# Power.net
KiCad netlist of a schematic drawn in Altium Designer
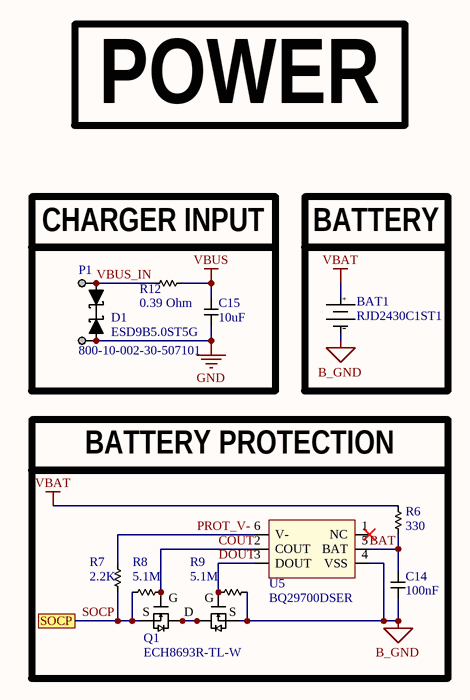
[diagram p0: Power.SchDoc]

(export (version "E")
  (design (tool "Eeschema 10.0.6"))
  (components
    (comp (ref "BAT1")
      (value "RJD2430C1ST1")
      (footprint "RJD2430C1ST1")
      (description "Coin, 24.5mm 3.7V Lithium-Ion Battery Rechargeable (Secondary) 110mAh")
      (libsource (lib "smLib") (part "RJD2430C1ST1"))
    )
    (comp (ref "C14")
      (value "100nF")
      (footprint "CAP_0603_HIGH")
      (description "0603 Capacitor")
      (libsource (lib "smLib") (part "Capacitor_0603"))
    )
    (comp (ref "C15")
      (value "10uF")
      (footprint "CAP_0603_HIGH")
      (description "0603 Capacitor")
      (libsource (lib "smLib") (part "Capacitor_0603"))
    )
    (comp (ref "D1")
      (value "ESD9B5.0ST5G")
      (footprint "ESD9B5.0ST5G")
      (description "TVS DIODE 5V SOD923")
      (libsource (lib "smLib") (part "ESD9B5.0ST5G"))
    )
    (comp (ref "P1")
      (value "800-10-002-30-507101")
      (footprint "800-10-002-30-507101")
      (description "2 Position Spring Mating Target Connector Surface Mount")
      (libsource (lib "smLib") (part "800-10-002-30-507101"))
    )
    (comp (ref "Q1")
      (value "ECH8693R-TL-W")
      (footprint "ECH8693R-TL-W")
      (description "Mosfet Array 2 N-Channel (Dual) Common Drain 24V 14A 1.4W Surface Mount SOT-28FL/ECH8")
      (libsource (lib "smLib") (part "ECH8693R-TL-W"))
    )
    (comp (ref "R6")
      (value "330")
      (footprint "RES_0603_HIGH")
      (description "0603 Resistor")
      (libsource (lib "smLib") (part "Resistor_0603"))
    )
    (comp (ref "R7")
      (value "2.2K")
      (footprint "RES_0603_HIGH")
      (description "0603 Resistor")
      (libsource (lib "smLib") (part "Resistor_0603"))
    )
    (comp (ref "R8")
      (value "5.1M")
      (footprint "RES_0603_HIGH")
      (description "0603 Resistor")
      (libsource (lib "smLib") (part "Resistor_0603"))
    )
    (comp (ref "R9")
      (value "5.1M")
      (footprint "RES_0603_HIGH")
      (description "0603 Resistor")
      (libsource (lib "smLib") (part "Resistor_0603"))
    )
    (comp (ref "R12")
      (value "0.39 Ohm")
      (footprint "RES_0805_HIGH")
      (description "0805 Resistor")
      (libsource (lib "smLib") (part "Resistor_0805"))
    )
    (comp (ref "U5")
      (value "BQ29700DSER")
      (footprint "BQ29700DSER")
      (description "Battery Battery Protection IC Lithium-Ion/Polymer 6-WSON (1.5x1.5)")
      (libsource (lib "smLib") (part "BQ29700DSER"))
    )
  )
  (nets
    (net (code "1") (name "/BAT") (class "Default")
      (node (ref "C14") (pin "1") (pinfunction "1_1") (pintype "passive"))
      (node (ref "R6") (pin "2") (pinfunction "2_2") (pintype "passive"))
      (node (ref "U5") (pin "5") (pinfunction "BAT_5") (pintype "passive"))
    )
    (net (code "2") (name "/COUT") (class "Default")
      (node (ref "Q1") (pin "2") (pinfunction "G1_2") (pintype "passive"))
      (node (ref "R8") (pin "1") (pinfunction "1_1") (pintype "passive"))
      (node (ref "U5") (pin "2") (pinfunction "COUT_2") (pintype "passive"))
    )
    (net (code "3") (name "/DOUT") (class "Default")
      (node (ref "Q1") (pin "4") (pinfunction "G2_4") (pintype "passive"))
      (node (ref "R9") (pin "2") (pinfunction "2_2") (pintype "passive"))
      (node (ref "U5") (pin "3") (pinfunction "DOUT_3") (pintype "passive"))
    )
    (net (code "4") (name "/PROT_V-") (class "Default")
      (node (ref "R7") (pin "1") (pinfunction "1_1") (pintype "passive"))
      (node (ref "U5") (pin "6") (pinfunction "V-_6") (pintype "passive"))
    )
    (net (code "5") (name "/SOCP") (class "Default")
      (node (ref "Q1") (pin "1") (pinfunction "S1_1") (pintype "passive"))
      (node (ref "R7") (pin "2") (pinfunction "2_2") (pintype "passive"))
      (node (ref "R8") (pin "2") (pinfunction "2_2") (pintype "passive"))
    )
    (net (code "6") (name "/VBUS_IN") (class "Default")
      (node (ref "D1") (pin "2") (pinfunction "2_2") (pintype "passive"))
      (node (ref "P1") (pin "1") (pinfunction "1_1") (pintype "passive"))
      (node (ref "R12") (pin "1") (pinfunction "1_1") (pintype "passive"))
    )
    (net (code "7") (name "B_GND") (class "Default")
      (node (ref "BAT1") (pin "2") (pinfunction "-_2") (pintype "passive"))
      (node (ref "C14") (pin "2") (pinfunction "2_2") (pintype "passive"))
      (node (ref "Q1") (pin "3") (pinfunction "S2_3") (pintype "passive"))
      (node (ref "R9") (pin "1") (pinfunction "1_1") (pintype "passive"))
      (node (ref "U5") (pin "4") (pinfunction "VSS_4") (pintype "passive"))
    )
    (net (code "8") (name "GND") (class "Default")
      (node (ref "C15") (pin "2") (pinfunction "2_2") (pintype "passive"))
      (node (ref "D1") (pin "1") (pinfunction "1_1") (pintype "passive"))
      (node (ref "P1") (pin "2") (pinfunction "2_2") (pintype "passive"))
    )
    (net (code "9") (name "Net-(Q1-D-Pad5)") (class "Default")
      (node (ref "Q1") (pin "5") (pinfunction "D_5") (pintype "passive"))
      (node (ref "Q1") (pin "6") (pinfunction "D_6") (pintype "passive"))
      (node (ref "Q1") (pin "7") (pinfunction "D_7") (pintype "passive"))
      (node (ref "Q1") (pin "8") (pinfunction "D_8") (pintype "passive"))
    )
    (net (code "10") (name "VBAT") (class "Default")
      (node (ref "BAT1") (pin "1") (pinfunction "+_1") (pintype "passive"))
      (node (ref "R6") (pin "1") (pinfunction "1_1") (pintype "passive"))
    )
    (net (code "11") (name "VBUS") (class "Default")
      (node (ref "C15") (pin "1") (pinfunction "1_1") (pintype "passive"))
      (node (ref "R12") (pin "2") (pinfunction "2_2") (pintype "passive"))
    )
    (net (code "12") (name "unconnected-(U5-NC-Pad1)") (class "Default")
      (node (ref "U5") (pin "1") (pinfunction "NC_1") (pintype "passive+no_connect"))
    )
  )
)
